# Sheet2.net
KiCad netlist of a schematic drawn in Altium Designer
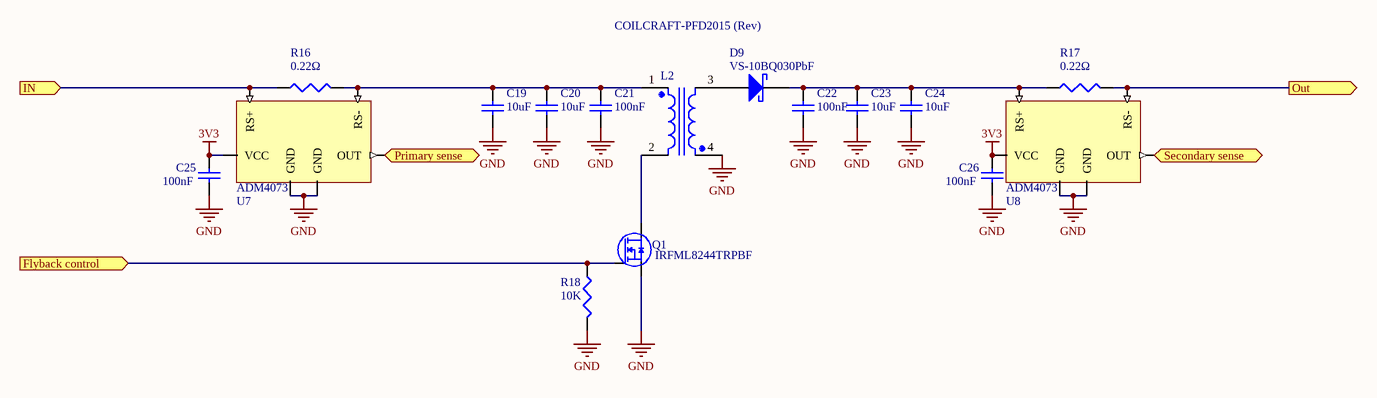
[diagram p0: Sheet2.SchDoc]

(export (version "E")
  (design (tool "Eeschema 10.0.6"))
  (components
    (comp (ref "C19")
      (value "10uF")
      (footprint "6-0805_M")
      (description "Capacitor (Semiconductor SIM Model)")
      (fields (field (name "Comment") "Cap Semi") (field (name "PUBLISHER") "Altium Limited"))
      (libsource (lib "Miscellaneous Devices") (part "Cap Semi"))
    )
    (comp (ref "C20")
      (value "10uF")
      (footprint "6-0805_M")
      (description "Capacitor (Semiconductor SIM Model)")
      (fields (field (name "Comment") "Cap Semi") (field (name "PUBLISHER") "Altium Limited"))
      (libsource (lib "Miscellaneous Devices") (part "Cap Semi"))
    )
    (comp (ref "C21")
      (value "100nF")
      (footprint "1608[0603]")
      (description "Capacitor (Semiconductor SIM Model)")
      (fields (field (name "Comment") "Cap Semi") (field (name "PUBLISHER") "Altium Limited"))
      (libsource (lib "Miscellaneous Devices") (part "Cap Semi"))
    )
    (comp (ref "C22")
      (value "100nF")
      (footprint "1608[0603]")
      (description "Capacitor (Semiconductor SIM Model)")
      (fields (field (name "Comment") "Cap Semi") (field (name "PUBLISHER") "Altium Limited"))
      (libsource (lib "Miscellaneous Devices") (part "Cap Semi"))
    )
    (comp (ref "C23")
      (value "10uF")
      (footprint "6-0805_M")
      (description "Capacitor (Semiconductor SIM Model)")
      (fields (field (name "Comment") "Cap Semi") (field (name "PUBLISHER") "Altium Limited"))
      (libsource (lib "Miscellaneous Devices") (part "Cap Semi"))
    )
    (comp (ref "C24")
      (value "10uF")
      (footprint "6-0805_M")
      (description "Capacitor (Semiconductor SIM Model)")
      (fields (field (name "Comment") "Cap Semi") (field (name "PUBLISHER") "Altium Limited"))
      (libsource (lib "Miscellaneous Devices") (part "Cap Semi"))
    )
    (comp (ref "C25")
      (value "100nF")
      (footprint "1608[0603]")
      (description "Capacitor (Semiconductor SIM Model)")
      (fields (field (name "Comment") "Cap Semi") (field (name "PUBLISHER") "Altium Limited"))
      (libsource (lib "Miscellaneous Devices") (part "Cap Semi"))
    )
    (comp (ref "C26")
      (value "100nF")
      (footprint "1608[0603]")
      (description "Capacitor (Semiconductor SIM Model)")
      (fields (field (name "Comment") "Cap Semi") (field (name "PUBLISHER") "Altium Limited"))
      (libsource (lib "Miscellaneous Devices") (part "Cap Semi"))
    )
    (comp (ref "D9")
      (value "VS-10BQ030PbF")
      (footprint "VS-10BQ030PbF - DIOM4435X24N")
      (libsource (lib "MargiLibrary") (part "VS-10BQ030PbF"))
    )
    (comp (ref "L2")
      (value "COILCRAFT-PFD2015 (Rev)")
      (footprint "PFD2015")
      (libsource (lib "MargiLibrary") (part "COILCRAFT-PFD2015 (Rev)"))
    )
    (comp (ref "Q1")
      (value "IRFML8244TRPBF")
      (footprint "SOT95P237X112-3N")
      (description "INTERNATIONAL RECTIFIER - IRFML8244TRPBF - N CH MOSFET, 25V, 5.8A, 3-SOT-23, FULL REEL")
      (fields (field (name "MANUFACTURER") "INTERNATIONAL RECTIFIER"))
      (libsource (lib "MargiLibrary") (part "IRFML8244TRPBF"))
    )
    (comp (ref "R16")
      (value "0.22Ω")
      (footprint "RESC6332")
      (description "Resistor")
      (fields (field (name "Comment") "Res3") (field (name "PUBLISHER") "Altium Limited"))
      (libsource (lib "Miscellaneous Devices") (part "Res3"))
    )
    (comp (ref "R17")
      (value "0.22Ω")
      (footprint "RESC6332")
      (description "Resistor")
      (fields (field (name "Comment") "Res3") (field (name "PUBLISHER") "Altium Limited"))
      (libsource (lib "Miscellaneous Devices") (part "Res3"))
    )
    (comp (ref "R18")
      (value "10K")
      (footprint "J1-0603")
      (description "Resistor")
      (fields (field (name "Comment") "Res3") (field (name "PUBLISHER") "Altium Limited"))
      (libsource (lib "Miscellaneous Devices") (part "Res3"))
    )
    (comp (ref "U7")
      (value "ADM4073")
      (footprint "ADM4073 - SOT95P280X145-6N")
      (libsource (lib "MargiLibrary") (part "ADM4073"))
    )
    (comp (ref "U8")
      (value "ADM4073")
      (footprint "ADM4073 - SOT95P280X145-6N")
      (libsource (lib "MargiLibrary") (part "ADM4073"))
    )
  )
  (nets
    (net (code "1") (name "/Flyback control") (class "Default")
      (node (ref "Q1") (pin "1") (pinfunction "G_1") (pintype "passive"))
      (node (ref "R18") (pin "1") (pinfunction "1_1") (pintype "passive"))
    )
    (net (code "2") (name "/IN") (class "Default")
      (node (ref "R16") (pin "1") (pinfunction "1_1") (pintype "passive"))
      (node (ref "U7") (pin "4") (pinfunction "RS+_4") (pintype "input"))
    )
    (net (code "3") (name "/Out") (class "Default")
      (node (ref "R17") (pin "2") (pinfunction "2_2") (pintype "passive"))
      (node (ref "U8") (pin "5") (pinfunction "RS-_5") (pintype "input"))
    )
    (net (code "4") (name "/Primary sense") (class "Default")
      (node (ref "U7") (pin "6") (pinfunction "OUT_6") (pintype "output"))
    )
    (net (code "5") (name "/Secondary sense") (class "Default")
      (node (ref "U8") (pin "6") (pinfunction "OUT_6") (pintype "output"))
    )
    (net (code "6") (name "3V3") (class "Default")
      (node (ref "C25") (pin "2") (pinfunction "2_2") (pintype "passive"))
      (node (ref "C26") (pin "2") (pinfunction "2_2") (pintype "passive"))
      (node (ref "U7") (pin "3") (pinfunction "VCC_3") (pintype "power_in"))
      (node (ref "U8") (pin "3") (pinfunction "VCC_3") (pintype "power_in"))
    )
    (net (code "7") (name "GND") (class "Default")
      (node (ref "C19") (pin "1") (pinfunction "1_1") (pintype "passive"))
      (node (ref "C20") (pin "1") (pinfunction "1_1") (pintype "passive"))
      (node (ref "C21") (pin "1") (pinfunction "1_1") (pintype "passive"))
      (node (ref "C22") (pin "1") (pinfunction "1_1") (pintype "passive"))
      (node (ref "C23") (pin "1") (pinfunction "1_1") (pintype "passive"))
      (node (ref "C24") (pin "1") (pinfunction "1_1") (pintype "passive"))
      (node (ref "C25") (pin "1") (pinfunction "1_1") (pintype "passive"))
      (node (ref "C26") (pin "1") (pinfunction "1_1") (pintype "passive"))
      (node (ref "L2") (pin "4") (pintype "passive"))
      (node (ref "Q1") (pin "2") (pinfunction "S_2") (pintype "passive"))
      (node (ref "R18") (pin "2") (pinfunction "2_2") (pintype "passive"))
      (node (ref "U7") (pin "1") (pinfunction "GND_1") (pintype "power_in"))
      (node (ref "U7") (pin "2") (pinfunction "GND_2") (pintype "power_in"))
      (node (ref "U8") (pin "1") (pinfunction "GND_1") (pintype "power_in"))
      (node (ref "U8") (pin "2") (pinfunction "GND_2") (pintype "power_in"))
    )
    (net (code "8") (name "Net-(D9-Pad2)") (class "Default")
      (node (ref "D9") (pin "2") (pintype "passive"))
      (node (ref "L2") (pin "3") (pintype "passive"))
    )
    (net (code "9") (name "Net-(Q1-D)") (class "Default")
      (node (ref "L2") (pin "2") (pintype "passive"))
      (node (ref "Q1") (pin "3") (pinfunction "D_3") (pintype "passive"))
    )
    (net (code "10") (name "Net-(U7-RS-)") (class "Default")
      (node (ref "C19") (pin "2") (pinfunction "2_2") (pintype "passive"))
      (node (ref "C20") (pin "2") (pinfunction "2_2") (pintype "passive"))
      (node (ref "C21") (pin "2") (pinfunction "2_2") (pintype "passive"))
      (node (ref "L2") (pin "1") (pintype "passive"))
      (node (ref "R16") (pin "2") (pinfunction "2_2") (pintype "passive"))
      (node (ref "U7") (pin "5") (pinfunction "RS-_5") (pintype "input"))
    )
    (net (code "11") (name "Net-(U8-RS+)") (class "Default")
      (node (ref "C22") (pin "2") (pinfunction "2_2") (pintype "passive"))
      (node (ref "C23") (pin "2") (pinfunction "2_2") (pintype "passive"))
      (node (ref "C24") (pin "2") (pinfunction "2_2") (pintype "passive"))
      (node (ref "D9") (pin "1") (pintype "passive"))
      (node (ref "R17") (pin "1") (pinfunction "1_1") (pintype "passive"))
      (node (ref "U8") (pin "4") (pinfunction "RS+_4") (pintype "input"))
    )
  )
)
